# bjt-cb.net
KiCad netlist of a schematic drawn in EAGLE
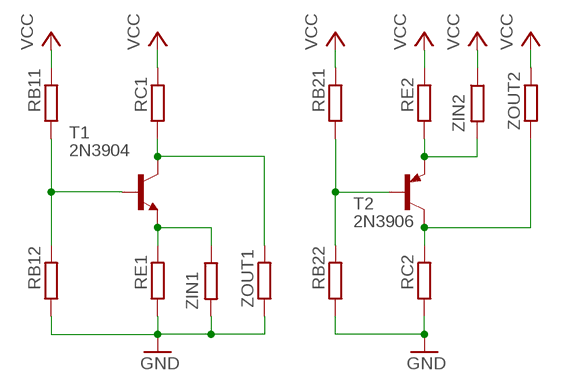
[diagram p0: schematic, sheet 1]

(export (version "E")
  (design (tool "Eeschema 10.0.6"))
  (components
    (comp (ref "RB11")
      (value "R-EU_0207/10")
      (footprint "eagle-import:0207_10")
      (libsource (lib "eagle-import") (part "R-EU_0207/10"))
    )
    (comp (ref "RB12")
      (value "R-EU_0207/10")
      (footprint "eagle-import:0207_10")
      (libsource (lib "eagle-import") (part "R-EU_0207/10"))
    )
    (comp (ref "RB21")
      (value "R-EU_0207/10")
      (footprint "eagle-import:0207_10")
      (libsource (lib "eagle-import") (part "R-EU_0207/10"))
    )
    (comp (ref "RB22")
      (value "R-EU_0207/10")
      (footprint "eagle-import:0207_10")
      (libsource (lib "eagle-import") (part "R-EU_0207/10"))
    )
    (comp (ref "RC1")
      (value "R-EU_0207/10")
      (footprint "eagle-import:0207_10")
      (libsource (lib "eagle-import") (part "R-EU_0207/10"))
    )
    (comp (ref "RC2")
      (value "R-EU_0207/10")
      (footprint "eagle-import:0207_10")
      (libsource (lib "eagle-import") (part "R-EU_0207/10"))
    )
    (comp (ref "RE1")
      (value "R-EU_0207/10")
      (footprint "eagle-import:0207_10")
      (libsource (lib "eagle-import") (part "R-EU_0207/10"))
    )
    (comp (ref "RE2")
      (value "R-EU_0207/10")
      (footprint "eagle-import:0207_10")
      (libsource (lib "eagle-import") (part "R-EU_0207/10"))
    )
    (comp (ref "T1")
      (value "2N3904")
      (footprint "eagle-import:TO92")
      (libsource (lib "eagle-import") (part "2N3904"))
    )
    (comp (ref "T2")
      (value "2N3906")
      (footprint "eagle-import:TO92")
      (libsource (lib "eagle-import") (part "2N3906"))
    )
    (comp (ref "ZIN1")
      (value "R-EU_0207/10")
      (footprint "eagle-import:0207_10")
      (libsource (lib "eagle-import") (part "R-EU_0207/10"))
    )
    (comp (ref "ZIN2")
      (value "R-EU_0207/10")
      (footprint "eagle-import:0207_10")
      (libsource (lib "eagle-import") (part "R-EU_0207/10"))
    )
    (comp (ref "ZOUT1")
      (value "R-EU_0207/10")
      (footprint "eagle-import:0207_10")
      (libsource (lib "eagle-import") (part "R-EU_0207/10"))
    )
    (comp (ref "ZOUT2")
      (value "R-EU_0207/10")
      (footprint "eagle-import:0207_10")
      (libsource (lib "eagle-import") (part "R-EU_0207/10"))
    )
  )
  (nets
    (net (code "1") (name "GND") (class "Default")
      (node (ref "RB12") (pin "1") (pinfunction "1_1") (pintype "passive"))
      (node (ref "RB22") (pin "1") (pinfunction "1_1") (pintype "passive"))
      (node (ref "RC2") (pin "1") (pinfunction "1_1") (pintype "passive"))
      (node (ref "RE1") (pin "1") (pinfunction "1_1") (pintype "passive"))
      (node (ref "ZIN1") (pin "2") (pinfunction "2_2") (pintype "passive"))
      (node (ref "ZOUT1") (pin "1") (pinfunction "1_1") (pintype "passive"))
    )
    (net (code "2") (name "Net-(T1-B)") (class "Default")
      (node (ref "RB11") (pin "1") (pinfunction "1_1") (pintype "passive"))
      (node (ref "RB12") (pin "2") (pinfunction "2_2") (pintype "passive"))
      (node (ref "T1") (pin "2") (pinfunction "B_2") (pintype "passive"))
    )
    (net (code "3") (name "Net-(T1-C)") (class "Default")
      (node (ref "RC1") (pin "1") (pinfunction "1_1") (pintype "passive"))
      (node (ref "T1") (pin "1") (pinfunction "C_1") (pintype "passive"))
      (node (ref "ZOUT1") (pin "2") (pinfunction "2_2") (pintype "passive"))
    )
    (net (code "4") (name "Net-(T1-E)") (class "Default")
      (node (ref "RE1") (pin "2") (pinfunction "2_2") (pintype "passive"))
      (node (ref "T1") (pin "3") (pinfunction "E_3") (pintype "passive"))
      (node (ref "ZIN1") (pin "1") (pinfunction "1_1") (pintype "passive"))
    )
    (net (code "5") (name "Net-(T2-B)") (class "Default")
      (node (ref "RB21") (pin "1") (pinfunction "1_1") (pintype "passive"))
      (node (ref "RB22") (pin "2") (pinfunction "2_2") (pintype "passive"))
      (node (ref "T2") (pin "2") (pinfunction "B_2") (pintype "passive"))
    )
    (net (code "6") (name "Net-(T2-C)") (class "Default")
      (node (ref "RC2") (pin "2") (pinfunction "2_2") (pintype "passive"))
      (node (ref "T2") (pin "1") (pinfunction "C_1") (pintype "passive"))
      (node (ref "ZOUT2") (pin "1") (pinfunction "1_1") (pintype "passive"))
    )
    (net (code "7") (name "Net-(T2-E)") (class "Default")
      (node (ref "RE2") (pin "1") (pinfunction "1_1") (pintype "passive"))
      (node (ref "T2") (pin "3") (pinfunction "E_3") (pintype "passive"))
      (node (ref "ZIN2") (pin "2") (pinfunction "2_2") (pintype "passive"))
    )
    (net (code "8") (name "VCC") (class "Default")
      (node (ref "RB11") (pin "2") (pinfunction "2_2") (pintype "passive"))
      (node (ref "RB21") (pin "2") (pinfunction "2_2") (pintype "passive"))
      (node (ref "RC1") (pin "2") (pinfunction "2_2") (pintype "passive"))
      (node (ref "RE2") (pin "2") (pinfunction "2_2") (pintype "passive"))
      (node (ref "ZIN2") (pin "1") (pinfunction "1_1") (pintype "passive"))
      (node (ref "ZOUT2") (pin "2") (pinfunction "2_2") (pintype "passive"))
    )
  )
)
